# giraffe-cjd.net
KiCad netlist of a schematic drawn in EAGLE
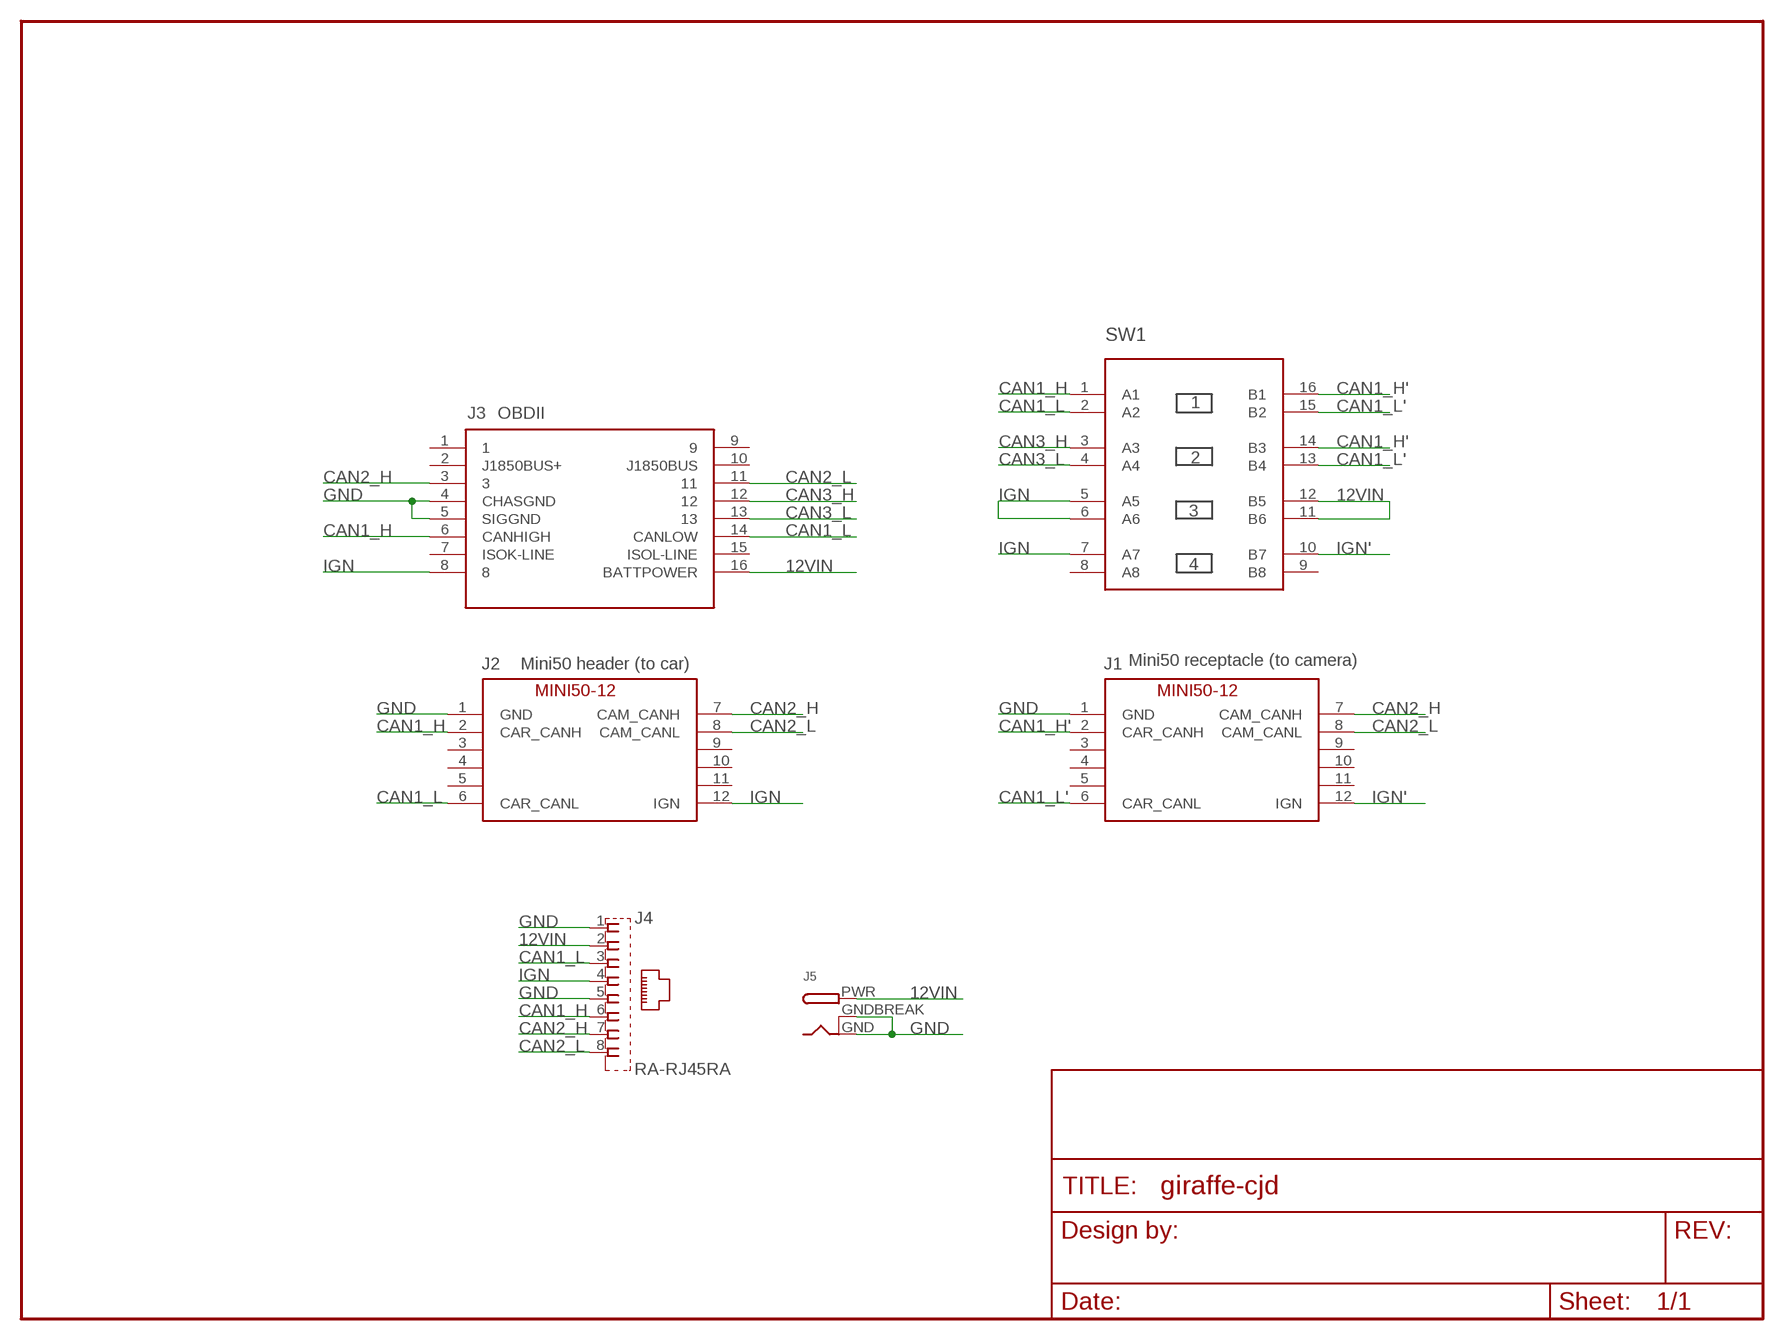
[diagram p0: schematic, sheet 1]

(export (version "E")
  (design (tool "Eeschema 10.0.6"))
  (components
    (comp (ref "FRAME1")
      (value "FRAME-LETTERNO_PACKAGE")
      (footprint "eagle-import:DUMMY")
      (fields (field (name "DESIGNER") "adhintz"))
      (libsource (lib "eagle-import") (part "FRAME-LETTERNO_PACKAGE"))
    )
    (comp (ref "J1")
      (value "MINI50MINI50-12-VERT")
      (footprint "eagle-import:MINI50-12")
      (libsource (lib "eagle-import") (part "MINI50MINI50-12-VERT"))
    )
    (comp (ref "J2")
      (value "MINI50MINI50-12-VERT")
      (footprint "eagle-import:MINI50-12")
      (libsource (lib "eagle-import") (part "MINI50MINI50-12-VERT"))
    )
    (comp (ref "J3")
      (value "OBDII-FEMALE-CUT")
      (footprint "eagle-import:OBDII-FEMALE-MIDCUT")
      (libsource (lib "eagle-import") (part "OBDII-FEMALE-CUT"))
    )
    (comp (ref "J4")
      (value "RA-RJ45RA")
      (footprint "eagle-import:RA-RJ45")
      (libsource (lib "eagle-import") (part "RA-RJ45RA"))
    )
    (comp (ref "J5")
      (value "DCBARRELPTH")
      (footprint "eagle-import:DCJACK_2MM_PTH")
      (libsource (lib "eagle-import") (part "DCBARRELPTH"))
    )
    (comp (ref "SW1")
      (value "4XDPSTSMT")
      (footprint "eagle-import:4-DPST")
      (libsource (lib "eagle-import") (part "4XDPSTSMT"))
    )
  )
  (nets
    (net (code "1") (name "/12VIN") (class "Default")
      (node (ref "J3") (pin "16") (pinfunction "BATTPOWER_16") (pintype "bidirectional"))
      (node (ref "J4") (pin "2") (pinfunction "2_2") (pintype "passive"))
      (node (ref "J5") (pin "PWR") (pinfunction "PWR_PWR") (pintype "power_in"))
      (node (ref "SW1") (pin "11") (pinfunction "B6_11") (pintype "bidirectional"))
      (node (ref "SW1") (pin "12") (pinfunction "B5_12") (pintype "bidirectional"))
    )
    (net (code "2") (name "/CAN1_H") (class "Default")
      (node (ref "J2") (pin "2") (pinfunction "CAR_CANH_2") (pintype "bidirectional"))
      (node (ref "J3") (pin "6") (pinfunction "CANHIGH_6") (pintype "bidirectional"))
      (node (ref "J4") (pin "6") (pinfunction "6_6") (pintype "passive"))
      (node (ref "SW1") (pin "1") (pinfunction "A1_1") (pintype "bidirectional"))
    )
    (net (code "3") (name "/CAN1_H'") (class "Default")
      (node (ref "J1") (pin "2") (pinfunction "CAR_CANH_2") (pintype "bidirectional"))
      (node (ref "SW1") (pin "14") (pinfunction "B3_14") (pintype "bidirectional"))
      (node (ref "SW1") (pin "16") (pinfunction "B1_16") (pintype "bidirectional"))
    )
    (net (code "4") (name "/CAN1_L") (class "Default")
      (node (ref "J2") (pin "6") (pinfunction "CAR_CANL_6") (pintype "bidirectional"))
      (node (ref "J3") (pin "14") (pinfunction "CANLOW_14") (pintype "bidirectional"))
      (node (ref "J4") (pin "3") (pinfunction "3_3") (pintype "passive"))
      (node (ref "SW1") (pin "2") (pinfunction "A2_2") (pintype "bidirectional"))
    )
    (net (code "5") (name "/CAN1_L'") (class "Default")
      (node (ref "J1") (pin "6") (pinfunction "CAR_CANL_6") (pintype "bidirectional"))
      (node (ref "SW1") (pin "13") (pinfunction "B4_13") (pintype "bidirectional"))
      (node (ref "SW1") (pin "15") (pinfunction "B2_15") (pintype "bidirectional"))
    )
    (net (code "6") (name "/CAN2_H") (class "Default")
      (node (ref "J1") (pin "7") (pinfunction "CAM_CANH_7") (pintype "bidirectional"))
      (node (ref "J2") (pin "7") (pinfunction "CAM_CANH_7") (pintype "bidirectional"))
      (node (ref "J3") (pin "3") (pinfunction "3_3") (pintype "bidirectional"))
      (node (ref "J4") (pin "7") (pinfunction "7_7") (pintype "passive"))
    )
    (net (code "7") (name "/CAN2_L") (class "Default")
      (node (ref "J1") (pin "8") (pinfunction "CAM_CANL_8") (pintype "bidirectional"))
      (node (ref "J2") (pin "8") (pinfunction "CAM_CANL_8") (pintype "bidirectional"))
      (node (ref "J3") (pin "11") (pinfunction "11_11") (pintype "bidirectional"))
      (node (ref "J4") (pin "8") (pinfunction "8_8") (pintype "passive"))
    )
    (net (code "8") (name "/CAN3_H") (class "Default")
      (node (ref "J3") (pin "12") (pinfunction "12_12") (pintype "bidirectional"))
      (node (ref "SW1") (pin "3") (pinfunction "A3_3") (pintype "bidirectional"))
    )
    (net (code "9") (name "/CAN3_L") (class "Default")
      (node (ref "J3") (pin "13") (pinfunction "13_13") (pintype "bidirectional"))
      (node (ref "SW1") (pin "4") (pinfunction "A4_4") (pintype "bidirectional"))
    )
    (net (code "10") (name "/GND") (class "Default")
      (node (ref "J1") (pin "1") (pinfunction "GND_1") (pintype "power_in"))
      (node (ref "J2") (pin "1") (pinfunction "GND_1") (pintype "power_in"))
      (node (ref "J3") (pin "4") (pinfunction "CHASGND_4") (pintype "bidirectional"))
      (node (ref "J3") (pin "5") (pinfunction "SIGGND_5") (pintype "bidirectional"))
      (node (ref "J4") (pin "1") (pinfunction "1_1") (pintype "passive"))
      (node (ref "J4") (pin "5") (pinfunction "5_5") (pintype "passive"))
      (node (ref "J5") (pin "GND") (pinfunction "GND_GND") (pintype "power_in"))
      (node (ref "J5") (pin "GNDBREAK") (pinfunction "GNDBREAK_GNDBREAK") (pintype "power_in"))
    )
    (net (code "11") (name "/IGN") (class "Default")
      (node (ref "J2") (pin "12") (pinfunction "IGN_12") (pintype "power_in"))
      (node (ref "J3") (pin "8") (pinfunction "8_8") (pintype "bidirectional"))
      (node (ref "J4") (pin "4") (pinfunction "4_4") (pintype "passive"))
      (node (ref "SW1") (pin "5") (pinfunction "A5_5") (pintype "bidirectional"))
      (node (ref "SW1") (pin "6") (pinfunction "A6_6") (pintype "bidirectional"))
      (node (ref "SW1") (pin "7") (pinfunction "A7_7") (pintype "bidirectional"))
    )
    (net (code "12") (name "/IGN'") (class "Default")
      (node (ref "J1") (pin "12") (pinfunction "IGN_12") (pintype "power_in"))
      (node (ref "SW1") (pin "10") (pinfunction "B7_10") (pintype "bidirectional"))
    )
    (net (code "13") (name "unconnected-(J1-Pad3)") (class "Default")
      (node (ref "J1") (pin "3") (pintype "bidirectional"))
    )
    (net (code "14") (name "unconnected-(J1-Pad4)") (class "Default")
      (node (ref "J1") (pin "4") (pintype "bidirectional"))
    )
    (net (code "15") (name "unconnected-(J1-Pad5)") (class "Default")
      (node (ref "J1") (pin "5") (pintype "bidirectional"))
    )
    (net (code "16") (name "unconnected-(J1-Pad9)") (class "Default")
      (node (ref "J1") (pin "9") (pintype "bidirectional"))
    )
    (net (code "17") (name "unconnected-(J1-Pad10)") (class "Default")
      (node (ref "J1") (pin "10") (pintype "bidirectional"))
    )
    (net (code "18") (name "unconnected-(J1-Pad11)") (class "Default")
      (node (ref "J1") (pin "11") (pintype "bidirectional"))
    )
    (net (code "19") (name "unconnected-(J2-Pad3)") (class "Default")
      (node (ref "J2") (pin "3") (pintype "bidirectional"))
    )
    (net (code "20") (name "unconnected-(J2-Pad4)") (class "Default")
      (node (ref "J2") (pin "4") (pintype "bidirectional"))
    )
    (net (code "21") (name "unconnected-(J2-Pad5)") (class "Default")
      (node (ref "J2") (pin "5") (pintype "bidirectional"))
    )
    (net (code "22") (name "unconnected-(J2-Pad9)") (class "Default")
      (node (ref "J2") (pin "9") (pintype "bidirectional"))
    )
    (net (code "23") (name "unconnected-(J2-Pad10)") (class "Default")
      (node (ref "J2") (pin "10") (pintype "bidirectional"))
    )
    (net (code "24") (name "unconnected-(J2-Pad11)") (class "Default")
      (node (ref "J2") (pin "11") (pintype "bidirectional"))
    )
    (net (code "25") (name "unconnected-(J3-ISOK-LINE-Pad7)") (class "Default")
      (node (ref "J3") (pin "7") (pinfunction "ISOK-LINE_7") (pintype "bidirectional"))
    )
    (net (code "26") (name "unconnected-(J3-ISOL-LINE-Pad15)") (class "Default")
      (node (ref "J3") (pin "15") (pinfunction "ISOL-LINE_15") (pintype "bidirectional"))
    )
    (net (code "27") (name "unconnected-(J3-J1850BUS+-Pad2)") (class "Default")
      (node (ref "J3") (pin "2") (pinfunction "J1850BUS+_2") (pintype "bidirectional"))
    )
    (net (code "28") (name "unconnected-(J3-J1850BUS-Pad10)") (class "Default")
      (node (ref "J3") (pin "10") (pinfunction "J1850BUS_10") (pintype "bidirectional"))
    )
    (net (code "29") (name "unconnected-(J3-Pad1)") (class "Default")
      (node (ref "J3") (pin "1") (pinfunction "1_1") (pintype "bidirectional"))
    )
    (net (code "30") (name "unconnected-(J3-Pad9)") (class "Default")
      (node (ref "J3") (pin "9") (pinfunction "9_9") (pintype "bidirectional"))
    )
    (net (code "31") (name "unconnected-(SW1-A8-Pad8)") (class "Default")
      (node (ref "SW1") (pin "8") (pinfunction "A8_8") (pintype "bidirectional"))
    )
    (net (code "32") (name "unconnected-(SW1-B8-Pad9)") (class "Default")
      (node (ref "SW1") (pin "9") (pinfunction "B8_9") (pintype "bidirectional"))
    )
  )
)
